# 3V3-CAN-UNISOLATED.net
KiCad netlist of a schematic drawn in Altium Designer
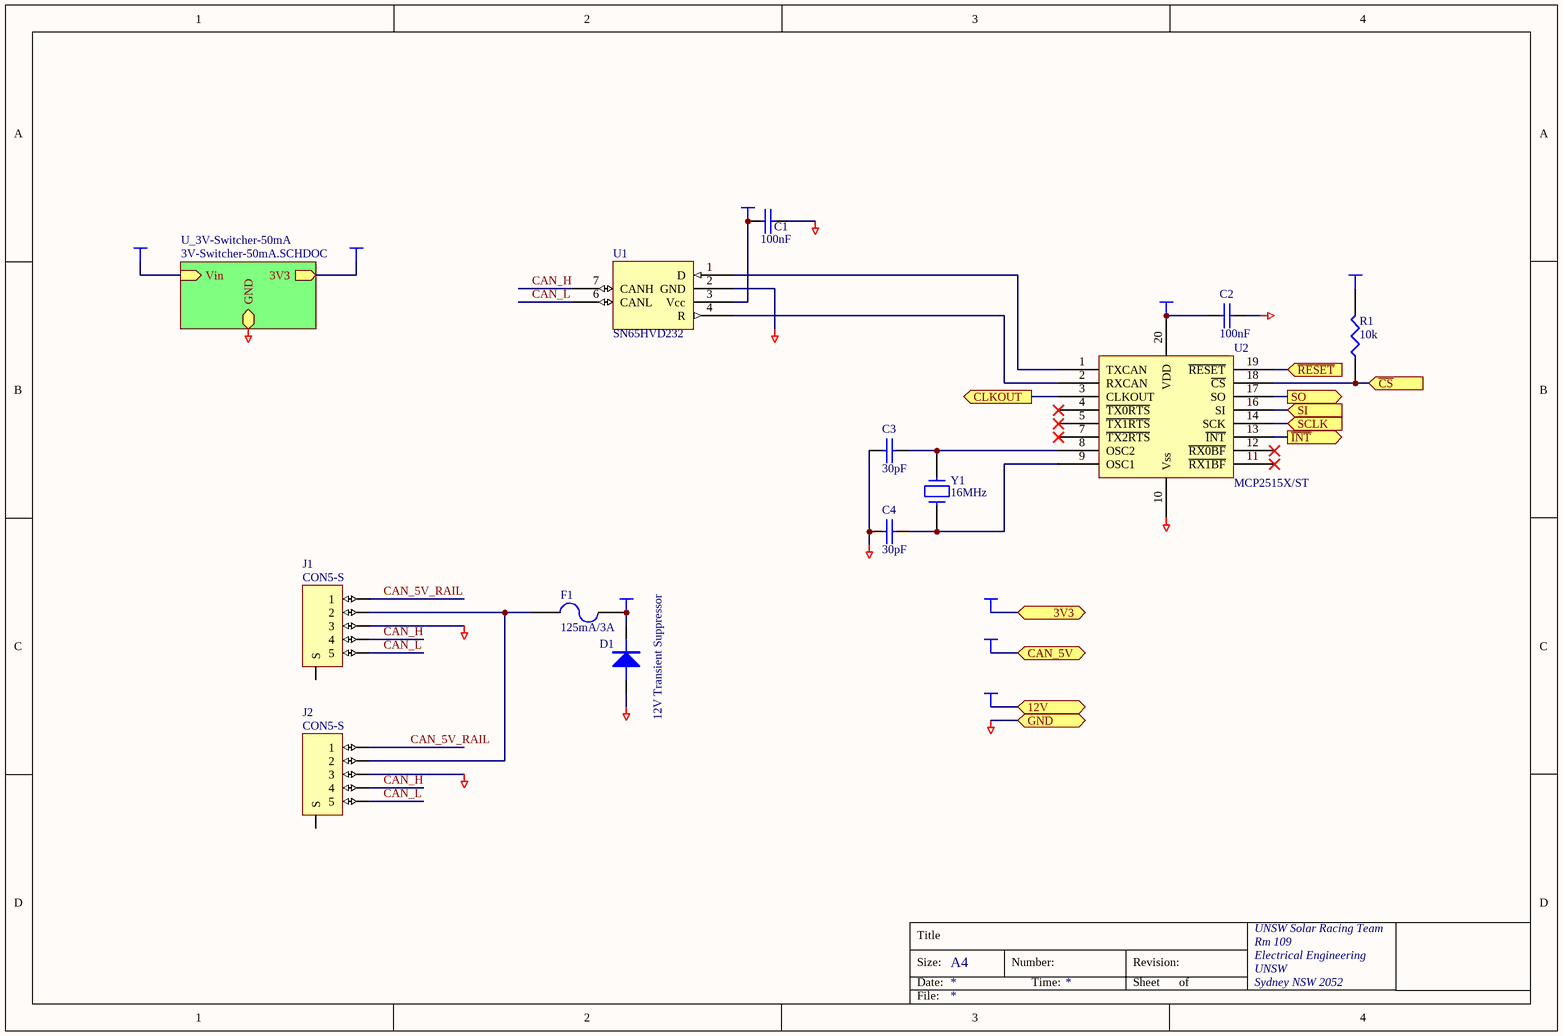
[diagram p0: 3V3-CAN-UNISOLATED.SchDoc]

(export (version "E")
  (design (tool "Eeschema 10.0.6"))
  (components
    (comp (ref "C1")
      (value "100nF")
      (footprint "0603")
      (description "Capacitor")
      (libsource (lib "*") (part "CAP"))
    )
    (comp (ref "C2")
      (value "100nF")
      (footprint "0603")
      (description "Capacitor")
      (libsource (lib "*") (part "CAP"))
    )
    (comp (ref "C3")
      (value "30pF")
      (footprint "0603")
      (description "Capacitor")
      (libsource (lib "*") (part "CAP"))
    )
    (comp (ref "C4")
      (value "30pF")
      (footprint "0603")
      (description "Capacitor")
      (libsource (lib "*") (part "CAP"))
    )
    (comp (ref "D1")
      (value "12V Transient Suppressor")
      (footprint "SMA")
      (description "Diode")
      (libsource (lib "RCLDQ") (part "DIODE"))
    )
    (comp (ref "F1")
      (value "125mA/3A")
      (footprint "LITTELFUSE-154")
      (description "Fuse")
      (libsource (lib "*") (part "FUSE2"))
    )
    (comp (ref "J1")
      (value "CON5-S")
      (footprint "TRIAD5F")
      (description "Connector, 2 pin, with shield @ S")
      (libsource (lib "*") (part "CON5-S"))
    )
    (comp (ref "J2")
      (value "CON5-S")
      (footprint "TRIAD5F")
      (description "Connector, 2 pin, with shield @ S")
      (libsource (lib "*") (part "CON5-S"))
    )
    (comp (ref "R1") (value "10k") (footprint "0603") (libsource (lib "*") (part "RES1")))
    (comp (ref "U1")
      (value "SN65HVD232")
      (footprint "SO8")
      (description "3.3V CAN Transciever")
      (libsource (lib "*") (part "SN65HVD232"))
    )
    (comp (ref "U2")
      (value "MCP2515X/ST")
      (footprint "TSSOP20")
      (description "MCP2510 CAN Controller")
      (libsource (lib "*") (part "MCP2510X/ST"))
    )
    (comp (ref "Y1")
      (value "16MHz")
      (footprint "HC49/4H")
      (description "Crystal")
      (libsource (lib "*") (part "CRYSTAL"))
    )
  )
  (nets
    (net (code "1") (name "/CAN_5V_RAIL") (class "Default")
      (node (ref "J1") (pin "1") (pinfunction "1_1") (pintype "bidirectional"))
      (node (ref "J2") (pin "1") (pinfunction "1_1") (pintype "bidirectional"))
    )
    (net (code "2") (name "/CAN_H") (class "Default")
      (node (ref "J1") (pin "4") (pinfunction "4_4") (pintype "bidirectional"))
      (node (ref "J2") (pin "4") (pinfunction "4_4") (pintype "bidirectional"))
      (node (ref "U1") (pin "7") (pinfunction "CANH_7") (pintype "bidirectional"))
    )
    (net (code "3") (name "/CAN_L") (class "Default")
      (node (ref "J1") (pin "5") (pinfunction "5_5") (pintype "bidirectional"))
      (node (ref "J2") (pin "5") (pinfunction "5_5") (pintype "bidirectional"))
      (node (ref "U1") (pin "6") (pinfunction "CANL_6") (pintype "bidirectional"))
    )
    (net (code "4") (name "/CLKOUT") (class "Default")
      (node (ref "U2") (pin "3") (pinfunction "CLKOUT_3") (pintype "passive"))
    )
    (net (code "5") (name "/CS") (class "Default")
      (node (ref "R1") (pin "1") (pinfunction "1_1") (pintype "passive"))
      (node (ref "U2") (pin "18") (pinfunction "CS_18") (pintype "passive"))
    )
    (net (code "6") (name "/INT") (class "Default")
      (node (ref "U2") (pin "13") (pinfunction "INT_13") (pintype "passive"))
    )
    (net (code "7") (name "/RESET") (class "Default")
      (node (ref "U2") (pin "19") (pinfunction "RESET_19") (pintype "passive"))
    )
    (net (code "8") (name "/SCLK") (class "Default")
      (node (ref "U2") (pin "14") (pinfunction "SCK_14") (pintype "passive"))
    )
    (net (code "9") (name "/SI") (class "Default")
      (node (ref "U2") (pin "16") (pinfunction "SI_16") (pintype "passive"))
    )
    (net (code "10") (name "/SO") (class "Default")
      (node (ref "U2") (pin "17") (pinfunction "SO_17") (pintype "passive"))
    )
    (net (code "11") (name "CAN+3V3") (class "Default")
      (node (ref "C1") (pin "2") (pinfunction "2_2") (pintype "passive"))
      (node (ref "C2") (pin "1") (pinfunction "1_1") (pintype "passive"))
      (node (ref "R1") (pin "2") (pinfunction "2_2") (pintype "passive"))
      (node (ref "U1") (pin "3") (pinfunction "Vcc_3") (pintype "power_in"))
      (node (ref "U2") (pin "20") (pinfunction "VDD_20") (pintype "passive"))
    )
    (net (code "13") (name "CAN+12V") (class "Default")
      (node (ref "D1") (pin "K") (pinfunction "K_K") (pintype "passive"))
      (node (ref "F1") (pin "2") (pinfunction "2_2") (pintype "passive"))
    )
    (net (code "14") (name "CANGND") (class "Default")
      (node (ref "C1") (pin "1") (pinfunction "1_1") (pintype "passive"))
      (node (ref "C2") (pin "2") (pinfunction "2_2") (pintype "passive"))
      (node (ref "C3") (pin "1") (pinfunction "1_1") (pintype "passive"))
      (node (ref "C4") (pin "1") (pinfunction "1_1") (pintype "passive"))
      (node (ref "D1") (pin "A") (pinfunction "A_A") (pintype "passive"))
      (node (ref "J1") (pin "3") (pinfunction "3_3") (pintype "bidirectional"))
      (node (ref "J2") (pin "3") (pinfunction "3_3") (pintype "bidirectional"))
      (node (ref "U1") (pin "2") (pinfunction "GND_2") (pintype "power_in"))
      (node (ref "U2") (pin "10") (pinfunction "Vss_10") (pintype "passive"))
    )
    (net (code "15") (name "Net-(F1-Pad1)") (class "Default")
      (node (ref "F1") (pin "1") (pinfunction "1_1") (pintype "passive"))
      (node (ref "J1") (pin "2") (pinfunction "2_2") (pintype "bidirectional"))
      (node (ref "J2") (pin "2") (pinfunction "2_2") (pintype "bidirectional"))
    )
    (net (code "16") (name "Net-(U1-D)") (class "Default")
      (node (ref "U1") (pin "1") (pinfunction "D_1") (pintype "input"))
      (node (ref "U2") (pin "1") (pinfunction "TXCAN_1") (pintype "passive"))
    )
    (net (code "17") (name "Net-(U1-R)") (class "Default")
      (node (ref "U1") (pin "4") (pinfunction "R_4") (pintype "output"))
      (node (ref "U2") (pin "2") (pinfunction "RXCAN_2") (pintype "passive"))
    )
    (net (code "18") (name "Net-(U2-OSC1)") (class "Default")
      (node (ref "C4") (pin "2") (pinfunction "2_2") (pintype "passive"))
      (node (ref "U2") (pin "9") (pinfunction "OSC1_9") (pintype "passive"))
      (node (ref "Y1") (pin "1") (pinfunction "1_1") (pintype "passive"))
    )
    (net (code "19") (name "Net-(U2-OSC2)") (class "Default")
      (node (ref "C3") (pin "2") (pinfunction "2_2") (pintype "passive"))
      (node (ref "U2") (pin "8") (pinfunction "OSC2_8") (pintype "passive"))
      (node (ref "Y1") (pin "2") (pinfunction "2_2") (pintype "passive"))
    )
    (net (code "20") (name "unconnected-(J1-S-Pad0)") (class "Default")
      (node (ref "J1") (pin "0") (pinfunction "S_0") (pintype "bidirectional"))
    )
    (net (code "21") (name "unconnected-(J2-S-Pad0)") (class "Default")
      (node (ref "J2") (pin "0") (pinfunction "S_0") (pintype "bidirectional"))
    )
    (net (code "22") (name "unconnected-(U2-RX0BF-Pad12)") (class "Default")
      (node (ref "U2") (pin "12") (pinfunction "RX0BF_12") (pintype "passive+no_connect"))
    )
    (net (code "23") (name "unconnected-(U2-RX1BF-Pad11)") (class "Default")
      (node (ref "U2") (pin "11") (pinfunction "RX1BF_11") (pintype "passive+no_connect"))
    )
    (net (code "24") (name "unconnected-(U2-TX0RTS-Pad4)") (class "Default")
      (node (ref "U2") (pin "4") (pinfunction "TX0RTS_4") (pintype "passive+no_connect"))
    )
    (net (code "25") (name "unconnected-(U2-TX1RTS-Pad5)") (class "Default")
      (node (ref "U2") (pin "5") (pinfunction "TX1RTS_5") (pintype "passive+no_connect"))
    )
    (net (code "26") (name "unconnected-(U2-TX2RTS-Pad7)") (class "Default")
      (node (ref "U2") (pin "7") (pinfunction "TX2RTS_7") (pintype "passive+no_connect"))
    )
  )
)
